# linear_voltage_regulator.net
KiCad netlist of a schematic drawn in EAGLE
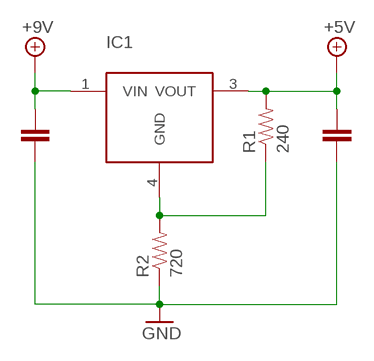
[diagram p0: schematic, sheet 1]

(export (version "E")
  (design (tool "Eeschema 10.0.6"))
  (components
    (comp (ref "C1")
      (value "0.1uF")
      (footprint "eagle-import:0402-CAP")
      (libsource (lib "eagle-import") (part "CAP0402-CAP"))
    )
    (comp (ref "C2")
      (value "1uF")
      (footprint "eagle-import:0402-CAP")
      (libsource (lib "eagle-import") (part "CAP0402-CAP"))
    )
    (comp (ref "IC1")
      (value "LM2931_FIXED")
      (footprint "eagle-import:DPAK")
      (libsource (lib "eagle-import") (part "LM2931_FIXED"))
    )
    (comp (ref "R1")
      (value "240")
      (footprint "eagle-import:0402-RES")
      (libsource (lib "eagle-import") (part "RESISTOR0402-RES"))
    )
    (comp (ref "R2")
      (value "720")
      (footprint "eagle-import:0402-RES")
      (libsource (lib "eagle-import") (part "RESISTOR0402-RES"))
    )
  )
  (nets
    (net (code "1") (name "+5V") (class "Default")
      (node (ref "C2") (pin "1") (pinfunction "1_1") (pintype "passive"))
      (node (ref "IC1") (pin "3") (pinfunction "VOUT_3") (pintype "bidirectional"))
      (node (ref "R1") (pin "2") (pinfunction "2_2") (pintype "passive"))
    )
    (net (code "2") (name "+9V") (class "Default")
      (node (ref "C1") (pin "1") (pinfunction "1_1") (pintype "passive"))
      (node (ref "IC1") (pin "1") (pinfunction "VIN_1") (pintype "bidirectional"))
    )
    (net (code "3") (name "GND") (class "Default")
      (node (ref "C1") (pin "2") (pinfunction "2_2") (pintype "passive"))
      (node (ref "C2") (pin "2") (pinfunction "2_2") (pintype "passive"))
      (node (ref "R2") (pin "1") (pinfunction "1_1") (pintype "passive"))
    )
    (net (code "4") (name "Net-(IC1-GND)") (class "Default")
      (node (ref "IC1") (pin "4") (pinfunction "GND_4") (pintype "bidirectional"))
      (node (ref "R1") (pin "1") (pinfunction "1_1") (pintype "passive"))
      (node (ref "R2") (pin "2") (pinfunction "2_2") (pintype "passive"))
    )
  )
)
